# 06-User_Interface.net
KiCad netlist of a schematic drawn in Altium Designer
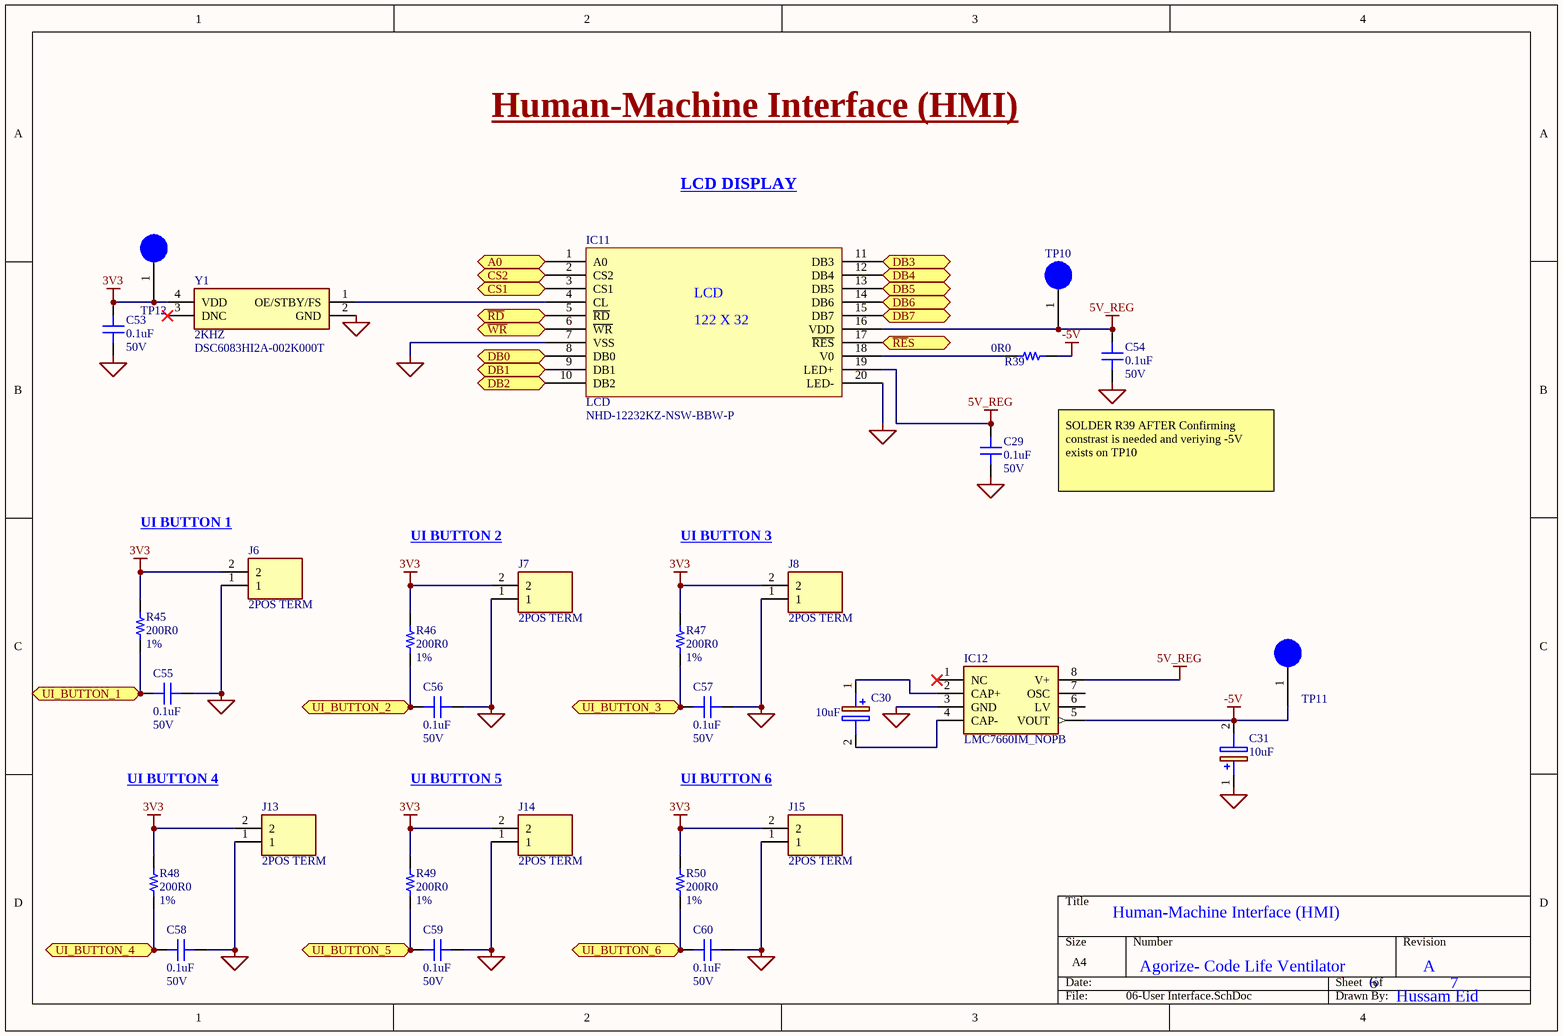
[diagram p0: 06-User Interface.SchDoc]

(export (version "E")
  (design (tool "Eeschema 10.0.6"))
  (components
    (comp (ref "C29")
      (value "0.1uF")
      (footprint "CAP 0603/1608")
      (description "CAP CER 0.1UF 50V X7R 0603")
      (fields (field (name "TOLERANCE") "20%") (field (name "VOLTAGE RATING") "50V"))
      (libsource (lib "Celestial Library Database") (part "Capacitor"))
    )
    (comp (ref "C30")
      (value "10uF")
      (footprint "SamacSys:CAPAE430X580N")
      (description "Capacitor Polarised")
      (libsource (lib "") (part "CS1A470M-CRC54_1"))
    )
    (comp (ref "C31")
      (value "10uF")
      (footprint "SamacSys:CAPAE430X580N")
      (description "Capacitor Polarised")
      (libsource (lib "*") (part "CS1A470M-CRC54"))
    )
    (comp (ref "C53")
      (value "0.1uF")
      (footprint "CAP 0603/1608")
      (description "CAP CER 0.1UF 50V X7R 0603")
      (fields (field (name "TOLERANCE") "20%") (field (name "VOLTAGE RATING") "50V"))
      (libsource (lib "Celestial Library Database") (part "Capacitor"))
    )
    (comp (ref "C54")
      (value "0.1uF")
      (footprint "CAP 0603/1608")
      (description "CAP CER 0.1UF 50V X7R 0603")
      (fields (field (name "TOLERANCE") "20%") (field (name "VOLTAGE RATING") "50V"))
      (libsource (lib "Celestial Library Database") (part "Capacitor"))
    )
    (comp (ref "C55")
      (value "0.1uF")
      (footprint "CAP 0603/1608")
      (description "CAP CER 0.1UF 50V X7R 0603")
      (fields (field (name "TOLERANCE") "20%") (field (name "VOLTAGE RATING") "50V"))
      (libsource (lib "Celestial Library Database") (part "Capacitor"))
    )
    (comp (ref "C56")
      (value "0.1uF")
      (footprint "CAP 0603/1608")
      (description "CAP CER 0.1UF 50V X7R 0603")
      (fields (field (name "TOLERANCE") "20%") (field (name "VOLTAGE RATING") "50V"))
      (libsource (lib "Celestial Library Database") (part "Capacitor"))
    )
    (comp (ref "C57")
      (value "0.1uF")
      (footprint "CAP 0603/1608")
      (description "CAP CER 0.1UF 50V X7R 0603")
      (fields (field (name "TOLERANCE") "20%") (field (name "VOLTAGE RATING") "50V"))
      (libsource (lib "Celestial Library Database") (part "Capacitor"))
    )
    (comp (ref "C58")
      (value "0.1uF")
      (footprint "CAP 0603/1608")
      (description "CAP CER 0.1UF 50V X7R 0603")
      (fields (field (name "TOLERANCE") "20%") (field (name "VOLTAGE RATING") "50V"))
      (libsource (lib "Celestial Library Database") (part "Capacitor"))
    )
    (comp (ref "C59")
      (value "0.1uF")
      (footprint "CAP 0603/1608")
      (description "CAP CER 0.1UF 50V X7R 0603")
      (fields (field (name "TOLERANCE") "20%") (field (name "VOLTAGE RATING") "50V"))
      (libsource (lib "Celestial Library Database") (part "Capacitor"))
    )
    (comp (ref "C60")
      (value "0.1uF")
      (footprint "CAP 0603/1608")
      (description "CAP CER 0.1UF 50V X7R 0603")
      (fields (field (name "TOLERANCE") "20%") (field (name "VOLTAGE RATING") "50V"))
      (libsource (lib "Celestial Library Database") (part "Capacitor"))
    )
    (comp (ref "IC11")
      (value "LCD")
      (footprint "LCD_CONN")
      (description "LCD MOD GRAPH 122X32 WH TRANSM")
      (fields (field (name "MANUFACTURER PART NUMBER 1") "NHD-12232KZ-NSW-BBW-P"))
      (libsource (lib "Schlib1") (part "Component_1"))
    )
    (comp (ref "IC12")
      (value "LMC7660IM_NOPB")
      (footprint "SamacSys:SOIC127P600X175-8N")
      (description "IC REG CHARGE PUMP INV 8SOIC")
      (fields
        (field (name "MOUSER PART NUMBER") "926-LMC7660IM/NOPB")
        (field (name "RS PART NUMBER") "5360212P")
      )
      (libsource (lib "*") (part "LMC7660IM_NOPB"))
    )
    (comp (ref "J6")
      (value "2POS TERM")
      (footprint "PcbLib1:SHDR2W110P0X500_1X2_1000X830X1140P")
      (description "TERM BLK 2POS SIDE ENTRY 5MM PCB")
      (fields (field (name "VOLTAGE") "300V"))
      (libsource (lib "*") (part "1935161"))
    )
    (comp (ref "J7")
      (value "2POS TERM")
      (footprint "PcbLib1:SHDR2W110P0X500_1X2_1000X830X1140P")
      (description "TERM BLK 2POS SIDE ENTRY 5MM PCB")
      (fields (field (name "VOLTAGE") "300V"))
      (libsource (lib "*") (part "1935161"))
    )
    (comp (ref "J8")
      (value "2POS TERM")
      (footprint "PcbLib1:SHDR2W110P0X500_1X2_1000X830X1140P")
      (description "TERM BLK 2POS SIDE ENTRY 5MM PCB")
      (fields (field (name "VOLTAGE") "300V"))
      (libsource (lib "*") (part "1935161"))
    )
    (comp (ref "J13")
      (value "2POS TERM")
      (footprint "PcbLib1:SHDR2W110P0X500_1X2_1000X830X1140P")
      (description "TERM BLK 2POS SIDE ENTRY 5MM PCB")
      (fields (field (name "VOLTAGE") "300V"))
      (libsource (lib "*") (part "1935161"))
    )
    (comp (ref "J14")
      (value "2POS TERM")
      (footprint "PcbLib1:SHDR2W110P0X500_1X2_1000X830X1140P")
      (description "TERM BLK 2POS SIDE ENTRY 5MM PCB")
      (fields (field (name "VOLTAGE") "300V"))
      (libsource (lib "*") (part "1935161"))
    )
    (comp (ref "J15")
      (value "2POS TERM")
      (footprint "PcbLib1:SHDR2W110P0X500_1X2_1000X830X1140P")
      (description "TERM BLK 2POS SIDE ENTRY 5MM PCB")
      (fields (field (name "VOLTAGE") "300V"))
      (libsource (lib "*") (part "1935161"))
    )
    (comp (ref "R39")
      (value "0R0")
      (footprint "RES 0603/1608")
      (description "RES SMD 0 OHM JUMPER 1/10W 0603")
      (fields (field (name "TOLERANCE") "0%"))
      (libsource (lib "Celestial Library Database") (part "Resistor"))
    )
    (comp (ref "R45")
      (value "200R0")
      (footprint "RES 1206/3216")
      (description "RES SMD 10K OHM 1% 1/4W 1206")
      (fields (field (name "TOLERANCE") "1%"))
      (libsource (lib "Celestial Library Database") (part "Resistor"))
    )
    (comp (ref "R46")
      (value "200R0")
      (footprint "RES 1206/3216")
      (description "RES SMD 10K OHM 1% 1/4W 1206")
      (fields (field (name "TOLERANCE") "1%"))
      (libsource (lib "Celestial Library Database") (part "Resistor"))
    )
    (comp (ref "R47")
      (value "200R0")
      (footprint "RES 1206/3216")
      (description "RES SMD 10K OHM 1% 1/4W 1206")
      (fields (field (name "TOLERANCE") "1%"))
      (libsource (lib "Celestial Library Database") (part "Resistor"))
    )
    (comp (ref "R48")
      (value "200R0")
      (footprint "RES 1206/3216")
      (description "RES SMD 10K OHM 1% 1/4W 1206")
      (fields (field (name "TOLERANCE") "1%"))
      (libsource (lib "Celestial Library Database") (part "Resistor"))
    )
    (comp (ref "R49")
      (value "200R0")
      (footprint "RES 1206/3216")
      (description "RES SMD 10K OHM 1% 1/4W 1206")
      (fields (field (name "TOLERANCE") "1%"))
      (libsource (lib "Celestial Library Database") (part "Resistor"))
    )
    (comp (ref "R50")
      (value "200R0")
      (footprint "RES 1206/3216")
      (description "RES SMD 10K OHM 1% 1/4W 1206")
      (fields (field (name "TOLERANCE") "1%"))
      (libsource (lib "Celestial Library Database") (part "Resistor"))
    )
    (comp (ref "TP10")
      (value "TP")
      (footprint "TP")
      (description "Test Point")
      (libsource (lib "Schlib1") (part "TP"))
    )
    (comp (ref "TP11")
      (value "TP")
      (footprint "TP")
      (description "Test Point")
      (libsource (lib "Schlib1") (part "TP"))
    )
    (comp (ref "TP12")
      (value "TP")
      (footprint "TP")
      (description "Test Point")
      (libsource (lib "Schlib1") (part "TP"))
    )
    (comp (ref "Y1")
      (value "2KHZ")
      (footprint "SamacSys:DSC6083HE1A032K800T")
      (description "MEMS OSC XO 2.0000KHZ CMOS SMD")
      (fields (field (name "MANUFACTURER PART NUMBER 1") "DSC6083HI2A-002K000T"))
      (libsource (lib "*") (part "DSC6083HE1A-032K800T"))
    )
  )
  (nets
    (net (code "1") (name "-5V") (class "Default")
      (node (ref "C31") (pin "2") (pinfunction "-_2") (pintype "passive"))
      (node (ref "IC12") (pin "5") (pinfunction "VOUT_5") (pintype "output"))
      (node (ref "R39") (pin "2") (pinfunction "2_2") (pintype "passive"))
      (node (ref "TP11") (pin "1") (pinfunction "1_1") (pintype "passive"))
    )
    (net (code "2") (name "/A0") (class "Default")
      (node (ref "IC11") (pin "1") (pinfunction "A0_1") (pintype "passive"))
    )
    (net (code "3") (name "/CS1") (class "Default")
      (node (ref "IC11") (pin "3") (pinfunction "CS1_3") (pintype "passive"))
    )
    (net (code "4") (name "/CS2") (class "Default")
      (node (ref "IC11") (pin "2") (pinfunction "CS2_2") (pintype "passive"))
    )
    (net (code "5") (name "/DB0") (class "Default")
      (node (ref "IC11") (pin "8") (pinfunction "DB0_8") (pintype "passive"))
    )
    (net (code "6") (name "/DB1") (class "Default")
      (node (ref "IC11") (pin "9") (pinfunction "DB1_9") (pintype "passive"))
    )
    (net (code "7") (name "/DB2") (class "Default")
      (node (ref "IC11") (pin "10") (pinfunction "DB2_10") (pintype "passive"))
    )
    (net (code "8") (name "/DB3") (class "Default")
      (node (ref "IC11") (pin "11") (pinfunction "DB3_11") (pintype "passive"))
    )
    (net (code "9") (name "/DB4") (class "Default")
      (node (ref "IC11") (pin "12") (pinfunction "DB4_12") (pintype "passive"))
    )
    (net (code "10") (name "/DB5") (class "Default")
      (node (ref "IC11") (pin "13") (pinfunction "DB5_13") (pintype "passive"))
    )
    (net (code "11") (name "/DB6") (class "Default")
      (node (ref "IC11") (pin "14") (pinfunction "DB6_14") (pintype "passive"))
    )
    (net (code "12") (name "/DB7") (class "Default")
      (node (ref "IC11") (pin "15") (pinfunction "DB7_15") (pintype "passive"))
    )
    (net (code "13") (name "/UI_BUTTON_1") (class "Default")
      (node (ref "C55") (pin "1") (pinfunction "1_1") (pintype "passive"))
      (node (ref "R45") (pin "1") (pinfunction "1_1") (pintype "passive"))
    )
    (net (code "14") (name "/UI_BUTTON_2") (class "Default")
      (node (ref "C56") (pin "1") (pinfunction "1_1") (pintype "passive"))
      (node (ref "R46") (pin "1") (pinfunction "1_1") (pintype "passive"))
    )
    (net (code "15") (name "/UI_BUTTON_3") (class "Default")
      (node (ref "C57") (pin "1") (pinfunction "1_1") (pintype "passive"))
      (node (ref "R47") (pin "1") (pinfunction "1_1") (pintype "passive"))
    )
    (net (code "16") (name "/UI_BUTTON_4") (class "Default")
      (node (ref "C58") (pin "1") (pinfunction "1_1") (pintype "passive"))
      (node (ref "R48") (pin "1") (pinfunction "1_1") (pintype "passive"))
    )
    (net (code "17") (name "/UI_BUTTON_5") (class "Default")
      (node (ref "C59") (pin "1") (pinfunction "1_1") (pintype "passive"))
      (node (ref "R49") (pin "1") (pinfunction "1_1") (pintype "passive"))
    )
    (net (code "18") (name "/UI_BUTTON_6") (class "Default")
      (node (ref "C60") (pin "1") (pinfunction "1_1") (pintype "passive"))
      (node (ref "R50") (pin "1") (pinfunction "1_1") (pintype "passive"))
    )
    (net (code "19") (name "/~{RD}") (class "Default")
      (node (ref "IC11") (pin "5") (pinfunction "~{RD}_5") (pintype "passive"))
    )
    (net (code "20") (name "/~{RE}S") (class "Default")
      (node (ref "IC11") (pin "17") (pinfunction "~{RES}_17") (pintype "passive"))
    )
    (net (code "21") (name "/~{WR}") (class "Default")
      (node (ref "IC11") (pin "6") (pinfunction "~{WR}_6") (pintype "passive"))
    )
    (net (code "22") (name "3V3") (class "Default")
      (node (ref "C53") (pin "1") (pinfunction "1_1") (pintype "passive"))
      (node (ref "J13") (pin "2") (pinfunction "2_2") (pintype "passive"))
      (node (ref "J14") (pin "2") (pinfunction "2_2") (pintype "passive"))
      (node (ref "J15") (pin "2") (pinfunction "2_2") (pintype "passive"))
      (node (ref "J6") (pin "2") (pinfunction "2_2") (pintype "passive"))
      (node (ref "J7") (pin "2") (pinfunction "2_2") (pintype "passive"))
      (node (ref "J8") (pin "2") (pinfunction "2_2") (pintype "passive"))
      (node (ref "R45") (pin "2") (pinfunction "2_2") (pintype "passive"))
      (node (ref "R46") (pin "2") (pinfunction "2_2") (pintype "passive"))
      (node (ref "R47") (pin "2") (pinfunction "2_2") (pintype "passive"))
      (node (ref "R48") (pin "2") (pinfunction "2_2") (pintype "passive"))
      (node (ref "R49") (pin "2") (pinfunction "2_2") (pintype "passive"))
      (node (ref "R50") (pin "2") (pinfunction "2_2") (pintype "passive"))
      (node (ref "TP12") (pin "1") (pinfunction "1_1") (pintype "passive"))
      (node (ref "Y1") (pin "4") (pinfunction "VDD_4") (pintype "passive"))
    )
    (net (code "23") (name "5V_REG") (class "Default")
      (node (ref "C29") (pin "1") (pinfunction "1_1") (pintype "passive"))
      (node (ref "C54") (pin "1") (pinfunction "1_1") (pintype "passive"))
      (node (ref "IC11") (pin "16") (pinfunction "VDD_16") (pintype "passive"))
      (node (ref "IC11") (pin "19") (pinfunction "LED+_19") (pintype "passive"))
      (node (ref "IC12") (pin "8") (pinfunction "V+_8") (pintype "passive"))
      (node (ref "TP10") (pin "1") (pinfunction "1_1") (pintype "passive"))
    )
    (net (code "24") (name "COM") (class "Default")
      (node (ref "C29") (pin "2") (pinfunction "2_2") (pintype "passive"))
      (node (ref "C31") (pin "1") (pinfunction "+_1") (pintype "passive"))
      (node (ref "C53") (pin "2") (pinfunction "2_2") (pintype "passive"))
      (node (ref "C54") (pin "2") (pinfunction "2_2") (pintype "passive"))
      (node (ref "C55") (pin "2") (pinfunction "2_2") (pintype "passive"))
      (node (ref "C56") (pin "2") (pinfunction "2_2") (pintype "passive"))
      (node (ref "C57") (pin "2") (pinfunction "2_2") (pintype "passive"))
      (node (ref "C58") (pin "2") (pinfunction "2_2") (pintype "passive"))
      (node (ref "C59") (pin "2") (pinfunction "2_2") (pintype "passive"))
      (node (ref "C60") (pin "2") (pinfunction "2_2") (pintype "passive"))
      (node (ref "IC11") (pin "20") (pinfunction "LED-_20") (pintype "passive"))
      (node (ref "IC11") (pin "7") (pinfunction "VSS_7") (pintype "passive"))
      (node (ref "IC12") (pin "3") (pinfunction "GND_3") (pintype "power_in"))
      (node (ref "J13") (pin "1") (pinfunction "1_1") (pintype "passive"))
      (node (ref "J14") (pin "1") (pinfunction "1_1") (pintype "passive"))
      (node (ref "J15") (pin "1") (pinfunction "1_1") (pintype "passive"))
      (node (ref "J6") (pin "1") (pinfunction "1_1") (pintype "passive"))
      (node (ref "J7") (pin "1") (pinfunction "1_1") (pintype "passive"))
      (node (ref "J8") (pin "1") (pinfunction "1_1") (pintype "passive"))
      (node (ref "Y1") (pin "2") (pinfunction "GND_2") (pintype "passive"))
    )
    (net (code "25") (name "Net-(C30-+)") (class "Default")
      (node (ref "C30") (pin "1") (pinfunction "+_1") (pintype "passive"))
      (node (ref "IC12") (pin "2") (pinfunction "CAP+_2") (pintype "passive"))
    )
    (net (code "26") (name "Net-(C30--)") (class "Default")
      (node (ref "C30") (pin "2") (pinfunction "-_2") (pintype "passive"))
      (node (ref "IC12") (pin "4") (pinfunction "CAP-_4") (pintype "passive"))
    )
    (net (code "27") (name "Net-(IC11-CL)") (class "Default")
      (node (ref "IC11") (pin "4") (pinfunction "CL_4") (pintype "passive"))
      (node (ref "Y1") (pin "1") (pinfunction "OE/STBY/FS_1") (pintype "passive"))
    )
    (net (code "28") (name "Net-(IC11-V0)") (class "Default")
      (node (ref "IC11") (pin "18") (pinfunction "V0_18") (pintype "passive"))
      (node (ref "R39") (pin "1") (pinfunction "1_1") (pintype "passive"))
    )
    (net (code "29") (name "unconnected-(IC12-LV-Pad6)") (class "Default")
      (node (ref "IC12") (pin "6") (pinfunction "LV_6") (pintype "passive"))
    )
    (net (code "30") (name "unconnected-(IC12-NC-Pad1)") (class "Default")
      (node (ref "IC12") (pin "1") (pinfunction "NC_1") (pintype "passive+no_connect"))
    )
    (net (code "31") (name "unconnected-(IC12-OSC-Pad7)") (class "Default")
      (node (ref "IC12") (pin "7") (pinfunction "OSC_7") (pintype "passive"))
    )
    (net (code "32") (name "unconnected-(Y1-DNC-Pad3)") (class "Default")
      (node (ref "Y1") (pin "3") (pinfunction "DNC_3") (pintype "passive+no_connect"))
    )
  )
)
